# Cpcis_connectors_P4_P5_P6.net
KiCad netlist of a schematic drawn in Altium Designer
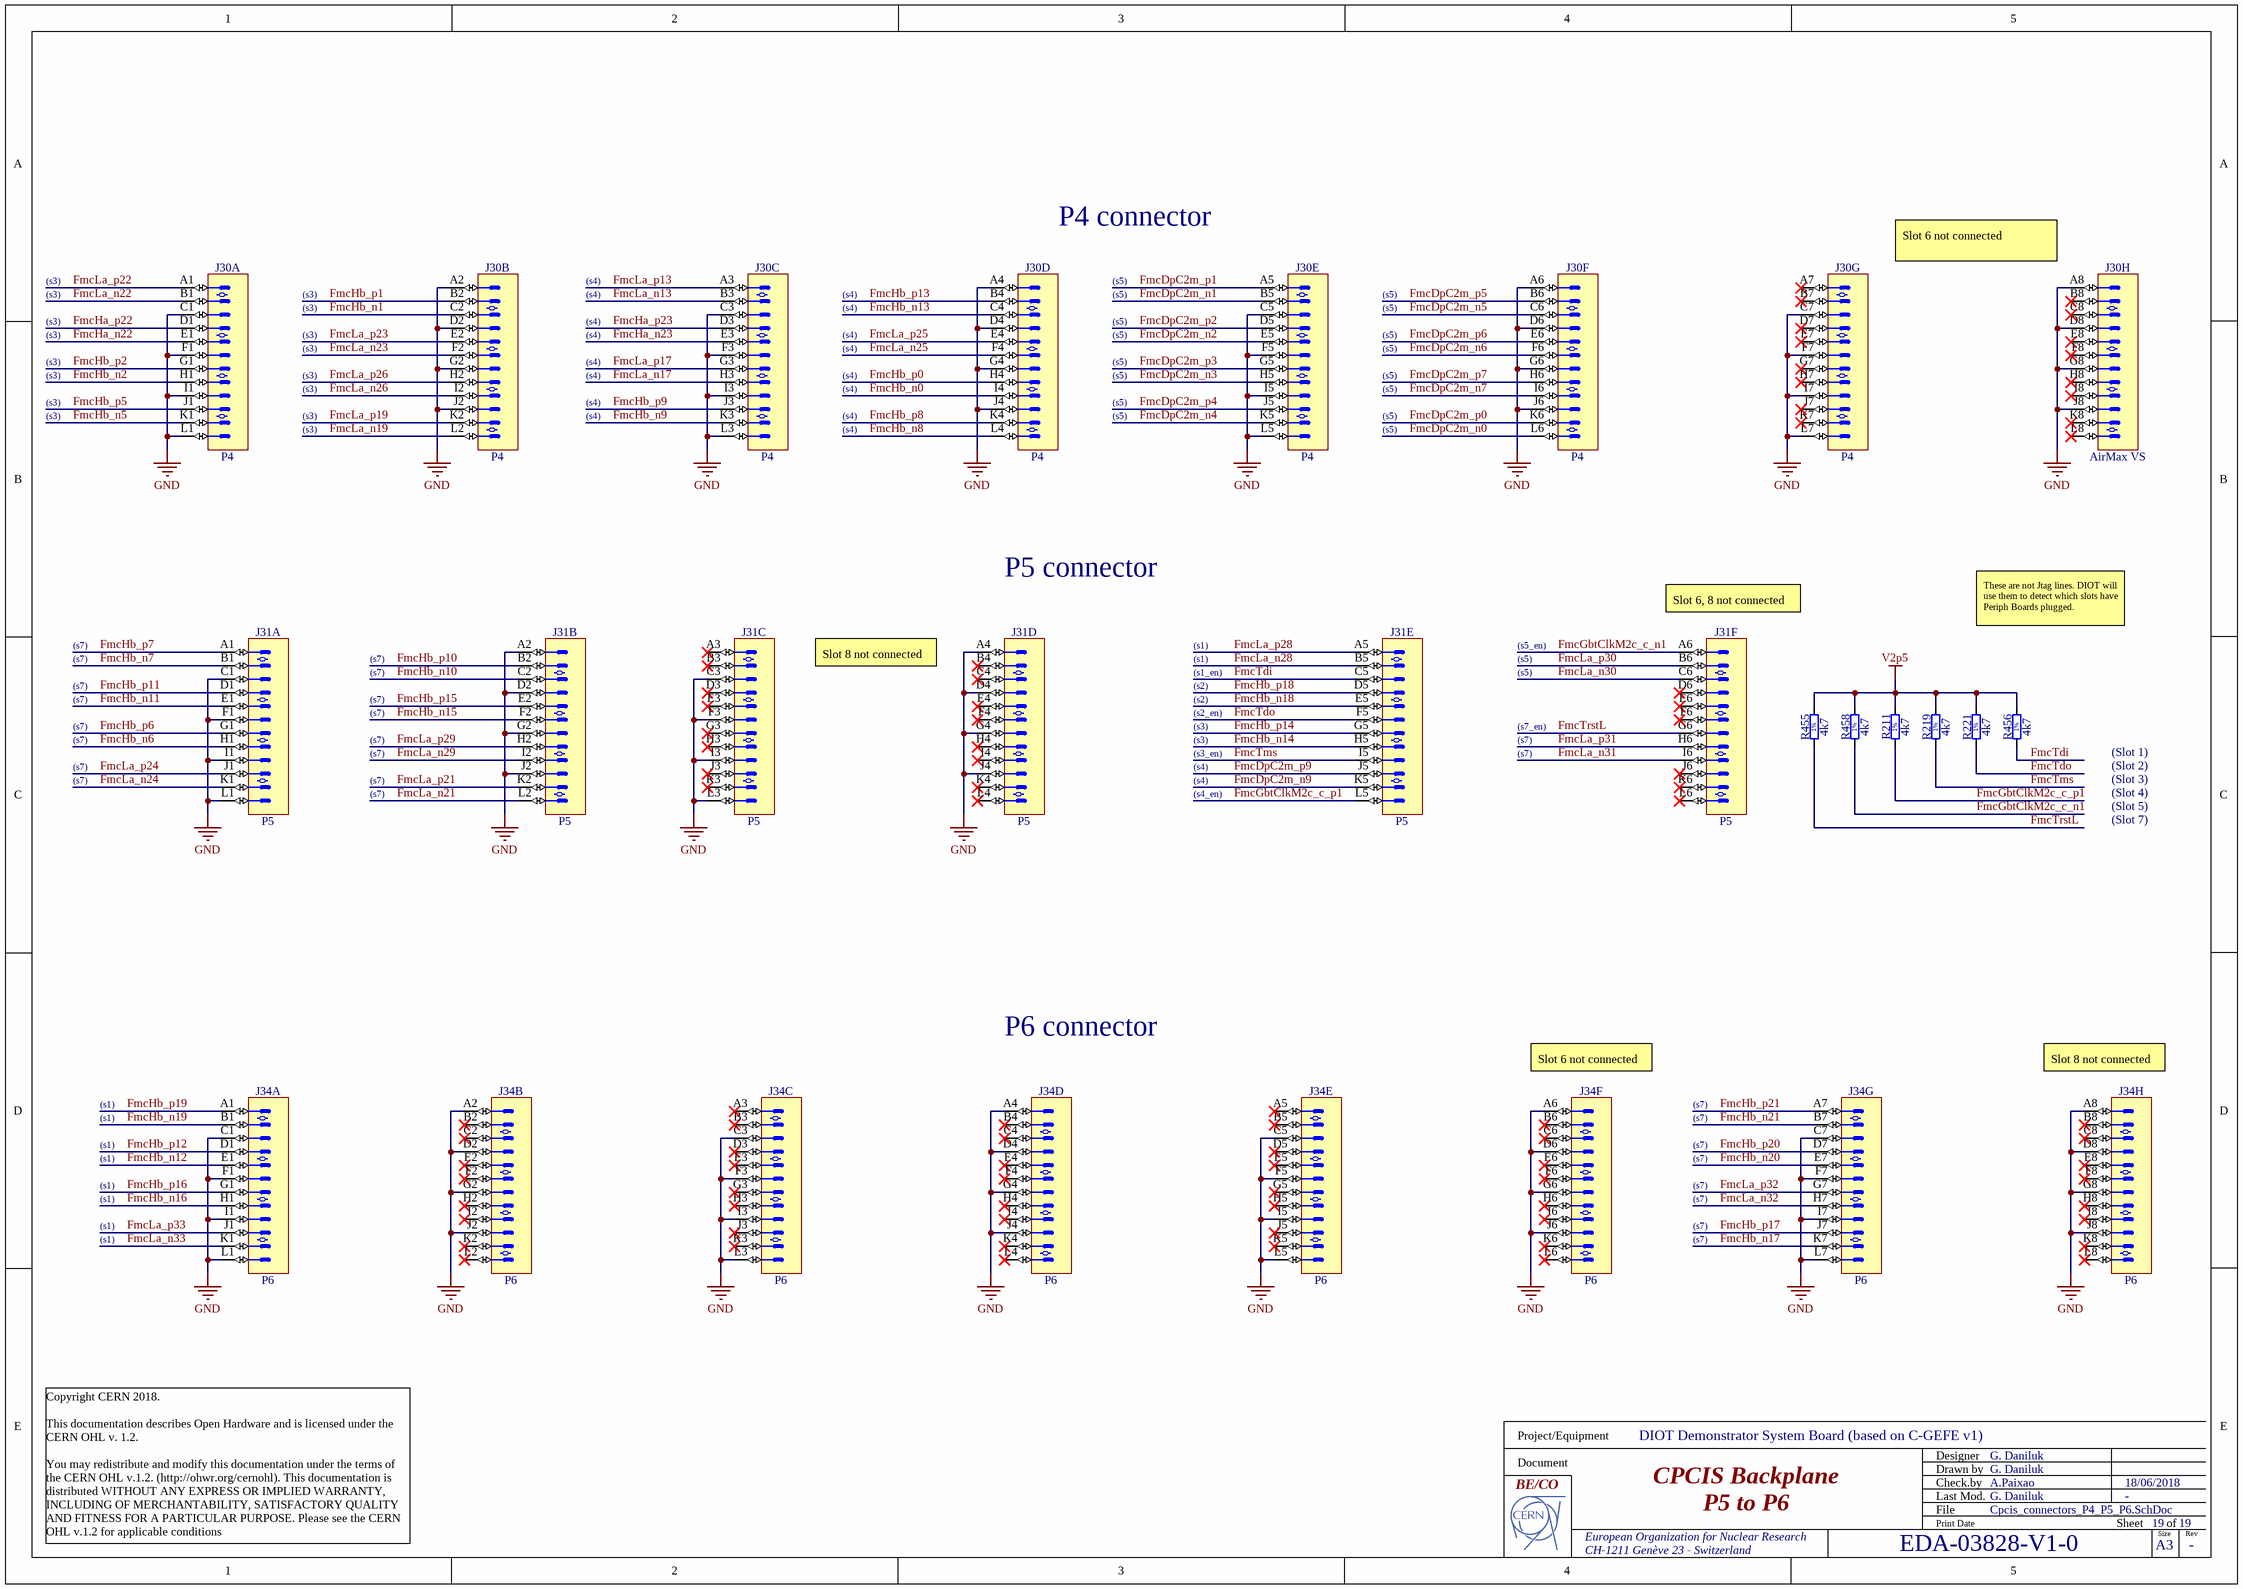
[diagram p0: Cpcis_connectors_P4_P5_P6.SchDoc]

(export (version "E")
  (design (tool "Eeschema 10.0.6"))
  (components
    (comp (ref "J30")
      (value "P4")
      (footprint "AMPHENOL_10052837-101LF")
      (description "96 Contacts Header, 8 Columns, 4 Pairs per Column")
      (fields
        (field (name "PART NUMBER") "AMPHENOL_10052837-101LF")
        (field (name "MANUFACTURER") "AMPHENOL")
        (field (name "AUTHOR") "CERN DEM MR")
      )
      (libsource (lib "Connectors") (part "AMPHENOL_10052837-101LF"))
    )
    (comp (ref "J31")
      (value "P5")
      (footprint "AMPHENOL_10052824-101LF")
      (description "72 Contacts Header, 6 Columns, 4 Pairs per Column")
      (fields
        (field (name "PART NUMBER") "AMPHENOL_10052824-101LF")
        (field (name "MANUFACTURER") "AMPHENOL")
        (field (name "AUTHOR") "CERN DEM JMW")
      )
      (libsource (lib "Connectors") (part "AMPHENOL_10052824-101LF"))
    )
    (comp (ref "J34")
      (value "P6")
      (footprint "AMPHENOL_10052838-101LF")
      (description "96 Contacts Header, 8 Columns, 4 Pairs per Column")
      (fields
        (field (name "PART NUMBER") "AMPHENOL_10052838-101LF")
        (field (name "MANUFACTURER") "AMPHENOL")
        (field (name "AUTHOR") "CERN DEM MR")
      )
      (libsource (lib "Connectors") (part "AMPHENOL_10052838-101LF"))
    )
    (comp (ref "R211")
      (value "4k7")
      (footprint "RESC1005X40N")
      (description "Resistor - 1%")
      (fields
        (field (name "PART NUMBER") "R0402_4K7_1%_0.0625W_100PPM")
        (field (name "POWER") "0.0625W")
        (field (name "AUTHOR") "CERN DEM JLC")
      )
      (libsource (lib "Resistors") (part "Resistor - 1%"))
    )
    (comp (ref "R219")
      (value "4k7")
      (footprint "RESC1005X40N")
      (description "Resistor - 1%")
      (fields
        (field (name "PART NUMBER") "R0402_4K7_1%_0.0625W_100PPM")
        (field (name "POWER") "0.0625W")
        (field (name "AUTHOR") "CERN DEM JLC")
      )
      (libsource (lib "Resistors") (part "Resistor - 1%"))
    )
    (comp (ref "R221")
      (value "4k7")
      (footprint "RESC1005X40N")
      (description "Resistor - 1%")
      (fields
        (field (name "PART NUMBER") "R0402_4K7_1%_0.0625W_100PPM")
        (field (name "POWER") "0.0625W")
        (field (name "AUTHOR") "CERN DEM JLC")
      )
      (libsource (lib "Resistors") (part "Resistor - 1%"))
    )
    (comp (ref "R455")
      (value "4k7")
      (footprint "RESC1005X40N")
      (description "Resistor - 1%")
      (fields
        (field (name "PART NUMBER") "R0402_4K7_1%_0.0625W_100PPM")
        (field (name "POWER") "0.0625W")
        (field (name "AUTHOR") "CERN DEM JLC")
      )
      (libsource (lib "Resistors") (part "Resistor - 1%"))
    )
    (comp (ref "R456")
      (value "4k7")
      (footprint "RESC1005X40N")
      (description "Resistor - 1%")
      (fields
        (field (name "PART NUMBER") "R0402_4K7_1%_0.0625W_100PPM")
        (field (name "POWER") "0.0625W")
        (field (name "AUTHOR") "CERN DEM JLC")
      )
      (libsource (lib "Resistors") (part "Resistor - 1%"))
    )
    (comp (ref "R458")
      (value "4k7")
      (footprint "RESC1005X40N")
      (description "Resistor - 1%")
      (fields
        (field (name "PART NUMBER") "R0402_4K7_1%_0.0625W_100PPM")
        (field (name "POWER") "0.0625W")
        (field (name "AUTHOR") "CERN DEM JLC")
      )
      (libsource (lib "Resistors") (part "Resistor - 1%"))
    )
  )
  (nets
    (net (code "1") (name "/FmcDpC2m_n0") (class "Default")
      (node (ref "J30") (pin "L6") (pinfunction "L6_L6") (pintype "bidirectional"))
    )
    (net (code "2") (name "/FmcDpC2m_n1") (class "Default")
      (node (ref "J30") (pin "B5") (pinfunction "B5_B5") (pintype "bidirectional"))
    )
    (net (code "3") (name "/FmcDpC2m_n2") (class "Default")
      (node (ref "J30") (pin "E5") (pinfunction "E5_E5") (pintype "bidirectional"))
    )
    (net (code "4") (name "/FmcDpC2m_n3") (class "Default")
      (node (ref "J30") (pin "H5") (pinfunction "H5_H5") (pintype "bidirectional"))
    )
    (net (code "5") (name "/FmcDpC2m_n4") (class "Default")
      (node (ref "J30") (pin "K5") (pinfunction "K5_K5") (pintype "bidirectional"))
    )
    (net (code "6") (name "/FmcDpC2m_n5") (class "Default")
      (node (ref "J30") (pin "C6") (pinfunction "C6_C6") (pintype "bidirectional"))
    )
    (net (code "7") (name "/FmcDpC2m_n6") (class "Default")
      (node (ref "J30") (pin "F6") (pinfunction "F6_F6") (pintype "bidirectional"))
    )
    (net (code "8") (name "/FmcDpC2m_n7") (class "Default")
      (node (ref "J30") (pin "I6") (pinfunction "I6_I6") (pintype "bidirectional"))
    )
    (net (code "9") (name "/FmcDpC2m_n9") (class "Default")
      (node (ref "J31") (pin "K5") (pinfunction "K5_K5") (pintype "bidirectional"))
    )
    (net (code "10") (name "/FmcDpC2m_p0") (class "Default")
      (node (ref "J30") (pin "K6") (pinfunction "K6_K6") (pintype "bidirectional"))
    )
    (net (code "11") (name "/FmcDpC2m_p1") (class "Default")
      (node (ref "J30") (pin "A5") (pinfunction "A5_A5") (pintype "bidirectional"))
    )
    (net (code "12") (name "/FmcDpC2m_p2") (class "Default")
      (node (ref "J30") (pin "D5") (pinfunction "D5_D5") (pintype "bidirectional"))
    )
    (net (code "13") (name "/FmcDpC2m_p3") (class "Default")
      (node (ref "J30") (pin "G5") (pinfunction "G5_G5") (pintype "bidirectional"))
    )
    (net (code "14") (name "/FmcDpC2m_p4") (class "Default")
      (node (ref "J30") (pin "J5") (pinfunction "J5_J5") (pintype "bidirectional"))
    )
    (net (code "15") (name "/FmcDpC2m_p5") (class "Default")
      (node (ref "J30") (pin "B6") (pinfunction "B6_B6") (pintype "bidirectional"))
    )
    (net (code "16") (name "/FmcDpC2m_p6") (class "Default")
      (node (ref "J30") (pin "E6") (pinfunction "E6_E6") (pintype "bidirectional"))
    )
    (net (code "17") (name "/FmcDpC2m_p7") (class "Default")
      (node (ref "J30") (pin "H6") (pinfunction "H6_H6") (pintype "bidirectional"))
    )
    (net (code "18") (name "/FmcDpC2m_p9") (class "Default")
      (node (ref "J31") (pin "J5") (pinfunction "J5_J5") (pintype "bidirectional"))
    )
    (net (code "19") (name "/FmcGbtClkM2c_c_n1") (class "Default")
      (node (ref "J31") (pin "A6") (pinfunction "A6_A6") (pintype "bidirectional"))
      (node (ref "R458") (pin "1") (pinfunction "1_1") (pintype "passive"))
    )
    (net (code "20") (name "/FmcGbtClkM2c_c_p1") (class "Default")
      (node (ref "J31") (pin "L5") (pinfunction "L5_L5") (pintype "bidirectional"))
      (node (ref "R211") (pin "1") (pinfunction "1_1") (pintype "passive"))
    )
    (net (code "21") (name "/FmcHa_n22") (class "Default")
      (node (ref "J30") (pin "E1") (pinfunction "E1_E1") (pintype "bidirectional"))
    )
    (net (code "22") (name "/FmcHa_n23") (class "Default")
      (node (ref "J30") (pin "E3") (pinfunction "E3_E3") (pintype "bidirectional"))
    )
    (net (code "23") (name "/FmcHa_p22") (class "Default")
      (node (ref "J30") (pin "D1") (pinfunction "D1_D1") (pintype "bidirectional"))
    )
    (net (code "24") (name "/FmcHa_p23") (class "Default")
      (node (ref "J30") (pin "D3") (pinfunction "D3_D3") (pintype "bidirectional"))
    )
    (net (code "25") (name "/FmcHb_n0") (class "Default")
      (node (ref "J30") (pin "I4") (pinfunction "I4_I4") (pintype "bidirectional"))
    )
    (net (code "26") (name "/FmcHb_n1") (class "Default")
      (node (ref "J30") (pin "C2") (pinfunction "C2_C2") (pintype "bidirectional"))
    )
    (net (code "27") (name "/FmcHb_n2") (class "Default")
      (node (ref "J30") (pin "H1") (pinfunction "H1_H1") (pintype "bidirectional"))
    )
    (net (code "28") (name "/FmcHb_n5") (class "Default")
      (node (ref "J30") (pin "K1") (pinfunction "K1_K1") (pintype "bidirectional"))
    )
    (net (code "29") (name "/FmcHb_n6") (class "Default")
      (node (ref "J31") (pin "H1") (pinfunction "H1_H1") (pintype "bidirectional"))
    )
    (net (code "30") (name "/FmcHb_n7") (class "Default")
      (node (ref "J31") (pin "B1") (pinfunction "B1_B1") (pintype "bidirectional"))
    )
    (net (code "31") (name "/FmcHb_n8") (class "Default")
      (node (ref "J30") (pin "L4") (pinfunction "L4_L4") (pintype "bidirectional"))
    )
    (net (code "32") (name "/FmcHb_n9") (class "Default")
      (node (ref "J30") (pin "K3") (pinfunction "K3_K3") (pintype "bidirectional"))
    )
    (net (code "33") (name "/FmcHb_n10") (class "Default")
      (node (ref "J31") (pin "C2") (pinfunction "C2_C2") (pintype "bidirectional"))
    )
    (net (code "34") (name "/FmcHb_n11") (class "Default")
      (node (ref "J31") (pin "E1") (pinfunction "E1_E1") (pintype "bidirectional"))
    )
    (net (code "35") (name "/FmcHb_n12") (class "Default")
      (node (ref "J34") (pin "E1") (pinfunction "E1_E1") (pintype "bidirectional"))
    )
    (net (code "36") (name "/FmcHb_n13") (class "Default")
      (node (ref "J30") (pin "C4") (pinfunction "C4_C4") (pintype "bidirectional"))
    )
    (net (code "37") (name "/FmcHb_n14") (class "Default")
      (node (ref "J31") (pin "H5") (pinfunction "H5_H5") (pintype "bidirectional"))
    )
    (net (code "38") (name "/FmcHb_n15") (class "Default")
      (node (ref "J31") (pin "F2") (pinfunction "F2_F2") (pintype "bidirectional"))
    )
    (net (code "39") (name "/FmcHb_n16") (class "Default")
      (node (ref "J34") (pin "H1") (pinfunction "H1_H1") (pintype "bidirectional"))
    )
    (net (code "40") (name "/FmcHb_n17") (class "Default")
      (node (ref "J34") (pin "K7") (pinfunction "K7_K7") (pintype "bidirectional"))
    )
    (net (code "41") (name "/FmcHb_n18") (class "Default")
      (node (ref "J31") (pin "E5") (pinfunction "E5_E5") (pintype "bidirectional"))
    )
    (net (code "42") (name "/FmcHb_n19") (class "Default")
      (node (ref "J34") (pin "B1") (pinfunction "B1_B1") (pintype "bidirectional"))
    )
    (net (code "43") (name "/FmcHb_n20") (class "Default")
      (node (ref "J34") (pin "E7") (pinfunction "E7_E7") (pintype "bidirectional"))
    )
    (net (code "44") (name "/FmcHb_n21") (class "Default")
      (node (ref "J34") (pin "B7") (pinfunction "B7_B7") (pintype "bidirectional"))
    )
    (net (code "45") (name "/FmcHb_p0") (class "Default")
      (node (ref "J30") (pin "H4") (pinfunction "H4_H4") (pintype "bidirectional"))
    )
    (net (code "46") (name "/FmcHb_p1") (class "Default")
      (node (ref "J30") (pin "B2") (pinfunction "B2_B2") (pintype "bidirectional"))
    )
    (net (code "47") (name "/FmcHb_p2") (class "Default")
      (node (ref "J30") (pin "G1") (pinfunction "G1_G1") (pintype "bidirectional"))
    )
    (net (code "48") (name "/FmcHb_p5") (class "Default")
      (node (ref "J30") (pin "J1") (pinfunction "J1_J1") (pintype "bidirectional"))
    )
    (net (code "49") (name "/FmcHb_p6") (class "Default")
      (node (ref "J31") (pin "G1") (pinfunction "G1_G1") (pintype "bidirectional"))
    )
    (net (code "50") (name "/FmcHb_p7") (class "Default")
      (node (ref "J31") (pin "A1") (pinfunction "A1_A1") (pintype "bidirectional"))
    )
    (net (code "51") (name "/FmcHb_p8") (class "Default")
      (node (ref "J30") (pin "K4") (pinfunction "K4_K4") (pintype "bidirectional"))
    )
    (net (code "52") (name "/FmcHb_p9") (class "Default")
      (node (ref "J30") (pin "J3") (pinfunction "J3_J3") (pintype "bidirectional"))
    )
    (net (code "53") (name "/FmcHb_p10") (class "Default")
      (node (ref "J31") (pin "B2") (pinfunction "B2_B2") (pintype "bidirectional"))
    )
    (net (code "54") (name "/FmcHb_p11") (class "Default")
      (node (ref "J31") (pin "D1") (pinfunction "D1_D1") (pintype "bidirectional"))
    )
    (net (code "55") (name "/FmcHb_p12") (class "Default")
      (node (ref "J34") (pin "D1") (pinfunction "D1_D1") (pintype "bidirectional"))
    )
    (net (code "56") (name "/FmcHb_p13") (class "Default")
      (node (ref "J30") (pin "B4") (pinfunction "B4_B4") (pintype "bidirectional"))
    )
    (net (code "57") (name "/FmcHb_p14") (class "Default")
      (node (ref "J31") (pin "G5") (pinfunction "G5_G5") (pintype "bidirectional"))
    )
    (net (code "58") (name "/FmcHb_p15") (class "Default")
      (node (ref "J31") (pin "E2") (pinfunction "E2_E2") (pintype "bidirectional"))
    )
    (net (code "59") (name "/FmcHb_p16") (class "Default")
      (node (ref "J34") (pin "G1") (pinfunction "G1_G1") (pintype "bidirectional"))
    )
    (net (code "60") (name "/FmcHb_p17") (class "Default")
      (node (ref "J34") (pin "J7") (pinfunction "J7_J7") (pintype "bidirectional"))
    )
    (net (code "61") (name "/FmcHb_p18") (class "Default")
      (node (ref "J31") (pin "D5") (pinfunction "D5_D5") (pintype "bidirectional"))
    )
    (net (code "62") (name "/FmcHb_p19") (class "Default")
      (node (ref "J34") (pin "A1") (pinfunction "A1_A1") (pintype "bidirectional"))
    )
    (net (code "63") (name "/FmcHb_p20") (class "Default")
      (node (ref "J34") (pin "D7") (pinfunction "D7_D7") (pintype "bidirectional"))
    )
    (net (code "64") (name "/FmcHb_p21") (class "Default")
      (node (ref "J34") (pin "A7") (pinfunction "A7_A7") (pintype "bidirectional"))
    )
    (net (code "65") (name "/FmcLa_n13") (class "Default")
      (node (ref "J30") (pin "B3") (pinfunction "B3_B3") (pintype "bidirectional"))
    )
    (net (code "66") (name "/FmcLa_n17") (class "Default")
      (node (ref "J30") (pin "H3") (pinfunction "H3_H3") (pintype "bidirectional"))
    )
    (net (code "67") (name "/FmcLa_n19") (class "Default")
      (node (ref "J30") (pin "L2") (pinfunction "L2_L2") (pintype "bidirectional"))
    )
    (net (code "68") (name "/FmcLa_n21") (class "Default")
      (node (ref "J31") (pin "L2") (pinfunction "L2_L2") (pintype "bidirectional"))
    )
    (net (code "69") (name "/FmcLa_n22") (class "Default")
      (node (ref "J30") (pin "B1") (pinfunction "B1_B1") (pintype "bidirectional"))
    )
    (net (code "70") (name "/FmcLa_n23") (class "Default")
      (node (ref "J30") (pin "F2") (pinfunction "F2_F2") (pintype "bidirectional"))
    )
    (net (code "71") (name "/FmcLa_n24") (class "Default")
      (node (ref "J31") (pin "K1") (pinfunction "K1_K1") (pintype "bidirectional"))
    )
    (net (code "72") (name "/FmcLa_n25") (class "Default")
      (node (ref "J30") (pin "F4") (pinfunction "F4_F4") (pintype "bidirectional"))
    )
    (net (code "73") (name "/FmcLa_n26") (class "Default")
      (node (ref "J30") (pin "I2") (pinfunction "I2_I2") (pintype "bidirectional"))
    )
    (net (code "74") (name "/FmcLa_n28") (class "Default")
      (node (ref "J31") (pin "B5") (pinfunction "B5_B5") (pintype "bidirectional"))
    )
    (net (code "75") (name "/FmcLa_n29") (class "Default")
      (node (ref "J31") (pin "I2") (pinfunction "I2_I2") (pintype "bidirectional"))
    )
    (net (code "76") (name "/FmcLa_n30") (class "Default")
      (node (ref "J31") (pin "C6") (pinfunction "C6_C6") (pintype "bidirectional"))
    )
    (net (code "77") (name "/FmcLa_n31") (class "Default")
      (node (ref "J31") (pin "I6") (pinfunction "I6_I6") (pintype "bidirectional"))
    )
    (net (code "78") (name "/FmcLa_n32") (class "Default")
      (node (ref "J34") (pin "H7") (pinfunction "H7_H7") (pintype "bidirectional"))
    )
    (net (code "79") (name "/FmcLa_n33") (class "Default")
      (node (ref "J34") (pin "K1") (pinfunction "K1_K1") (pintype "bidirectional"))
    )
    (net (code "80") (name "/FmcLa_p13") (class "Default")
      (node (ref "J30") (pin "A3") (pinfunction "A3_A3") (pintype "bidirectional"))
    )
    (net (code "81") (name "/FmcLa_p17") (class "Default")
      (node (ref "J30") (pin "G3") (pinfunction "G3_G3") (pintype "bidirectional"))
    )
    (net (code "82") (name "/FmcLa_p19") (class "Default")
      (node (ref "J30") (pin "K2") (pinfunction "K2_K2") (pintype "bidirectional"))
    )
    (net (code "83") (name "/FmcLa_p21") (class "Default")
      (node (ref "J31") (pin "K2") (pinfunction "K2_K2") (pintype "bidirectional"))
    )
    (net (code "84") (name "/FmcLa_p22") (class "Default")
      (node (ref "J30") (pin "A1") (pinfunction "A1_A1") (pintype "bidirectional"))
    )
    (net (code "85") (name "/FmcLa_p23") (class "Default")
      (node (ref "J30") (pin "E2") (pinfunction "E2_E2") (pintype "bidirectional"))
    )
    (net (code "86") (name "/FmcLa_p24") (class "Default")
      (node (ref "J31") (pin "J1") (pinfunction "J1_J1") (pintype "bidirectional"))
    )
    (net (code "87") (name "/FmcLa_p25") (class "Default")
      (node (ref "J30") (pin "E4") (pinfunction "E4_E4") (pintype "bidirectional"))
    )
    (net (code "88") (name "/FmcLa_p26") (class "Default")
      (node (ref "J30") (pin "H2") (pinfunction "H2_H2") (pintype "bidirectional"))
    )
    (net (code "89") (name "/FmcLa_p28") (class "Default")
      (node (ref "J31") (pin "A5") (pinfunction "A5_A5") (pintype "bidirectional"))
    )
    (net (code "90") (name "/FmcLa_p29") (class "Default")
      (node (ref "J31") (pin "H2") (pinfunction "H2_H2") (pintype "bidirectional"))
    )
    (net (code "91") (name "/FmcLa_p30") (class "Default")
      (node (ref "J31") (pin "B6") (pinfunction "B6_B6") (pintype "bidirectional"))
    )
    (net (code "92") (name "/FmcLa_p31") (class "Default")
      (node (ref "J31") (pin "H6") (pinfunction "H6_H6") (pintype "bidirectional"))
    )
    (net (code "93") (name "/FmcLa_p32") (class "Default")
      (node (ref "J34") (pin "G7") (pinfunction "G7_G7") (pintype "bidirectional"))
    )
    (net (code "94") (name "/FmcLa_p33") (class "Default")
      (node (ref "J34") (pin "J1") (pinfunction "J1_J1") (pintype "bidirectional"))
    )
    (net (code "95") (name "/FmcTdi") (class "Default")
      (node (ref "J31") (pin "C5") (pinfunction "C5_C5") (pintype "bidirectional"))
      (node (ref "R456") (pin "1") (pinfunction "1_1") (pintype "passive"))
    )
    (net (code "96") (name "/FmcTdo") (class "Default")
      (node (ref "J31") (pin "F5") (pinfunction "F5_F5") (pintype "bidirectional"))
      (node (ref "R221") (pin "1") (pinfunction "1_1") (pintype "passive"))
    )
    (net (code "97") (name "/FmcTms") (class "Default")
      (node (ref "J31") (pin "I5") (pinfunction "I5_I5") (pintype "bidirectional"))
      (node (ref "R219") (pin "1") (pinfunction "1_1") (pintype "passive"))
    )
    (net (code "98") (name "/FmcTrstL") (class "Default")
      (node (ref "J31") (pin "G6") (pinfunction "G6_G6") (pintype "bidirectional"))
      (node (ref "R455") (pin "1") (pinfunction "1_1") (pintype "passive"))
    )
    (net (code "99") (name "GND") (class "Default")
      (node (ref "J30") (pin "A2") (pinfunction "A2_A2") (pintype "bidirectional"))
      (node (ref "J30") (pin "A4") (pinfunction "A4_A4") (pintype "bidirectional"))
      (node (ref "J30") (pin "A6") (pinfunction "A6_A6") (pintype "bidirectional"))
      (node (ref "J30") (pin "A8") (pinfunction "A8_A8") (pintype "bidirectional"))
      (node (ref "J30") (pin "C1") (pinfunction "C1_C1") (pintype "bidirectional"))
      (node (ref "J30") (pin "C3") (pinfunction "C3_C3") (pintype "bidirectional"))
      (node (ref "J30") (pin "C5") (pinfunction "C5_C5") (pintype "bidirectional"))
      (node (ref "J30") (pin "C7") (pinfunction "C7_C7") (pintype "bidirectional"))
      (node (ref "J30") (pin "D2") (pinfunction "D2_D2") (pintype "bidirectional"))
      (node (ref "J30") (pin "D4") (pinfunction "D4_D4") (pintype "bidirectional"))
      (node (ref "J30") (pin "D6") (pinfunction "D6_D6") (pintype "bidirectional"))
      (node (ref "J30") (pin "D8") (pinfunction "D8_D8") (pintype "bidirectional"))
      (node (ref "J30") (pin "F1") (pinfunction "F1_F1") (pintype "bidirectional"))
      (node (ref "J30") (pin "F3") (pinfunction "F3_F3") (pintype "bidirectional"))
      (node (ref "J30") (pin "F5") (pinfunction "F5_F5") (pintype "bidirectional"))
      (node (ref "J30") (pin "F7") (pinfunction "F7_F7") (pintype "bidirectional"))
      (node (ref "J30") (pin "G2") (pinfunction "G2_G2") (pintype "bidirectional"))
      (node (ref "J30") (pin "G4") (pinfunction "G4_G4") (pintype "bidirectional"))
      (node (ref "J30") (pin "G6") (pinfunction "G6_G6") (pintype "bidirectional"))
      (node (ref "J30") (pin "G8") (pinfunction "G8_G8") (pintype "bidirectional"))
      (node (ref "J30") (pin "I1") (pinfunction "I1_I1") (pintype "bidirectional"))
      (node (ref "J30") (pin "I3") (pinfunction "I3_I3") (pintype "bidirectional"))
      (node (ref "J30") (pin "I5") (pinfunction "I5_I5") (pintype "bidirectional"))
      (node (ref "J30") (pin "I7") (pinfunction "I7_I7") (pintype "bidirectional"))
      (node (ref "J30") (pin "J2") (pinfunction "J2_J2") (pintype "bidirectional"))
      (node (ref "J30") (pin "J4") (pinfunction "J4_J4") (pintype "bidirectional"))
      (node (ref "J30") (pin "J6") (pinfunction "J6_J6") (pintype "bidirectional"))
      (node (ref "J30") (pin "J8") (pinfunction "J8_J8") (pintype "bidirectional"))
      (node (ref "J30") (pin "L1") (pinfunction "L1_L1") (pintype "bidirectional"))
      (node (ref "J30") (pin "L3") (pinfunction "L3_L3") (pintype "bidirectional"))
      (node (ref "J30") (pin "L5") (pinfunction "L5_L5") (pintype "bidirectional"))
      (node (ref "J30") (pin "L7") (pinfunction "L7_L7") (pintype "bidirectional"))
      (node (ref "J31") (pin "A2") (pinfunction "A2_A2") (pintype "bidirectional"))
      (node (ref "J31") (pin "A4") (pinfunction "A4_A4") (pintype "bidirectional"))
      (node (ref "J31") (pin "C1") (pinfunction "C1_C1") (pintype "bidirectional"))
      (node (ref "J31") (pin "C3") (pinfunction "C3_C3") (pintype "bidirectional"))
      (node (ref "J31") (pin "D2") (pinfunction "D2_D2") (pintype "bidirectional"))
      (node (ref "J31") (pin "D4") (pinfunction "D4_D4") (pintype "bidirectional"))
      (node (ref "J31") (pin "F1") (pinfunction "F1_F1") (pintype "bidirectional"))
      (node (ref "J31") (pin "F3") (pinfunction "F3_F3") (pintype "bidirectional"))
      (node (ref "J31") (pin "G2") (pinfunction "G2_G2") (pintype "bidirectional"))
      (node (ref "J31") (pin "G4") (pinfunction "G4_G4") (pintype "bidirectional"))
      (node (ref "J31") (pin "I1") (pinfunction "I1_I1") (pintype "bidirectional"))
      (node (ref "J31") (pin "I3") (pinfunction "I3_I3") (pintype "bidirectional"))
      (node (ref "J31") (pin "J2") (pinfunction "J2_J2") (pintype "bidirectional"))
      (node (ref "J31") (pin "J4") (pinfunction "J4_J4") (pintype "bidirectional"))
      (node (ref "J31") (pin "L1") (pinfunction "L1_L1") (pintype "bidirectional"))
      (node (ref "J31") (pin "L3") (pinfunction "L3_L3") (pintype "bidirectional"))
      (node (ref "J34") (pin "A2") (pinfunction "A2_A2") (pintype "bidirectional"))
      (node (ref "J34") (pin "A4") (pinfunction "A4_A4") (pintype "bidirectional"))
      (node (ref "J34") (pin "A6") (pinfunction "A6_A6") (pintype "bidirectional"))
      (node (ref "J34") (pin "A8") (pinfunction "A8_A8") (pintype "bidirectional"))
      (node (ref "J34") (pin "C1") (pinfunction "C1_C1") (pintype "bidirectional"))
      (node (ref "J34") (pin "C3") (pinfunction "C3_C3") (pintype "bidirectional"))
      (node (ref "J34") (pin "C5") (pinfunction "C5_C5") (pintype "bidirectional"))
      (node (ref "J34") (pin "C7") (pinfunction "C7_C7") (pintype "bidirectional"))
      (node (ref "J34") (pin "D2") (pinfunction "D2_D2") (pintype "bidirectional"))
      (node (ref "J34") (pin "D4") (pinfunction "D4_D4") (pintype "bidirectional"))
      (node (ref "J34") (pin "D6") (pinfunction "D6_D6") (pintype "bidirectional"))
      (node (ref "J34") (pin "D8") (pinfunction "D8_D8") (pintype "bidirectional"))
      (node (ref "J34") (pin "F1") (pinfunction "F1_F1") (pintype "bidirectional"))
      (node (ref "J34") (pin "F3") (pinfunction "F3_F3") (pintype "bidirectional"))
      (node (ref "J34") (pin "F5") (pinfunction "F5_F5") (pintype "bidirectional"))
      (node (ref "J34") (pin "F7") (pinfunction "F7_F7") (pintype "bidirectional"))
      (node (ref "J34") (pin "G2") (pinfunction "G2_G2") (pintype "bidirectional"))
      (node (ref "J34") (pin "G4") (pinfunction "G4_G4") (pintype "bidirectional"))
      (node (ref "J34") (pin "G6") (pinfunction "G6_G6") (pintype "bidirectional"))
      (node (ref "J34") (pin "G8") (pinfunction "G8_G8") (pintype "bidirectional"))
      (node (ref "J34") (pin "I1") (pinfunction "I1_I1") (pintype "bidirectional"))
      (node (ref "J34") (pin "I3") (pinfunction "I3_I3") (pintype "bidirectional"))
      (node (ref "J34") (pin "I5") (pinfunction "I5_I5") (pintype "bidirectional"))
      (node (ref "J34") (pin "I7") (pinfunction "I7_I7") (pintype "bidirectional"))
      (node (ref "J34") (pin "J2") (pinfunction "J2_J2") (pintype "bidirectional"))
      (node (ref "J34") (pin "J4") (pinfunction "J4_J4") (pintype "bidirectional"))
      (node (ref "J34") (pin "J6") (pinfunction "J6_J6") (pintype "bidirectional"))
      (node (ref "J34") (pin "J8") (pinfunction "J8_J8") (pintype "bidirectional"))
      (node (ref "J34") (pin "L1") (pinfunction "L1_L1") (pintype "bidirectional"))
      (node (ref "J34") (pin "L3") (pinfunction "L3_L3") (pintype "bidirectional"))
      (node (ref "J34") (pin "L5") (pinfunction "L5_L5") (pintype "bidirectional"))
      (node (ref "J34") (pin "L7") (pinfunction "L7_L7") (pintype "bidirectional"))
    )
    (net (code "100") (name "V2p5") (class "Default")
      (node (ref "R211") (pin "2") (pinfunction "2_2") (pintype "passive"))
      (node (ref "R219") (pin "2") (pinfunction "2_2") (pintype "passive"))
      (node (ref "R221") (pin "2") (pinfunction "2_2") (pintype "passive"))
      (node (ref "R455") (pin "2") (pinfunction "2_2") (pintype "passive"))
      (node (ref "R456") (pin "2") (pinfunction "2_2") (pintype "passive"))
      (node (ref "R458") (pin "2") (pinfunction "2_2") (pintype "passive"))
    )
    (net (code "101") (name "unconnected-(J30-PadA7)") (class "Default")
      (node (ref "J30") (pin "A7") (pinfunction "A7_A7") (pintype "bidirectional+no_connect"))
    )
    (net (code "102") (name "unconnected-(J30-PadB7)") (class "Default")
      (node (ref "J30") (pin "B7") (pinfunction "B7_B7") (pintype "bidirectional+no_connect"))
    )
    (net (code "103") (name "unconnected-(J30-PadB8)") (class "Default")
      (node (ref "J30") (pin "B8") (pinfunction "B8_B8") (pintype "bidirectional+no_connect"))
    )
    (net (code "104") (name "unconnected-(J30-PadC8)") (class "Default")
      (node (ref "J30") (pin "C8") (pinfunction "C8_C8") (pintype "bidirectional+no_connect"))
    )
    (net (code "105") (name "unconnected-(J30-PadD7)") (class "Default")
      (node (ref "J30") (pin "D7") (pinfunction "D7_D7") (pintype "bidirectional+no_connect"))
    )
    (net (code "106") (name "unconnected-(J30-PadE7)") (class "Default")
      (node (ref "J30") (pin "E7") (pinfunction "E7_E7") (pintype "bidirectional+no_connect"))
    )
    (net (code "107") (name "unconnected-(J30-PadE8)") (class "Default")
      (node (ref "J30") (pin "E8") (pinfunction "E8_E8") (pintype "bidirectional+no_connect"))
    )
    (net (code "108") (name "unconnected-(J30-PadF8)") (class "Default")
      (node (ref "J30") (pin "F8") (pinfunction "F8_F8") (pintype "bidirectional+no_connect"))
    )
    (net (code "109") (name "unconnected-(J30-PadG7)") (class "Default")
      (node (ref "J30") (pin "G7") (pinfunction "G7_G7") (pintype "bidirectional+no_connect"))
    )
    (net (code "110") (name "unconnected-(J30-PadH7)") (class "Default")
      (node (ref "J30") (pin "H7") (pinfunction "H7_H7") (pintype "bidirectional+no_connect"))
    )
    (net (code "111") (name "unconnected-(J30-PadH8)") (class "Default")
      (node (ref "J30") (pin "H8") (pinfunction "H8_H8") (pintype "bidirectional+no_connect"))
    )
    (net (code "112") (name "unconnected-(J30-PadI8)") (class "Default")
      (node (ref "J30") (pin "I8") (pinfunction "I8_I8") (pintype "bidirectional+no_connect"))
    )
    (net (code "113") (name "unconnected-(J30-PadJ7)") (class "Default")
      (node (ref "J30") (pin "J7") (pinfunction "J7_J7") (pintype "bidirectional+no_connect"))
    )
    (net (code "114") (name "unconnected-(J30-PadK7)") (class "Default")
      (node (ref "J30") (pin "K7") (pinfunction "K7_K7") (pintype "bidirectional+no_connect"))
    )
    (net (code "115") (name "unconnected-(J30-PadK8)") (class "Default")
      (node (ref "J30") (pin "K8") (pinfunction "K8_K8") (pintype "bidirectional+no_connect"))
    )
    (net (code "116") (name "unconnected-(J30-PadL8)") (class "Default")
      (node (ref "J30") (pin "L8") (pinfunction "L8_L8") (pintype "bidirectional+no_connect"))
    )
    (net (code "117") (name "unconnected-(J31-PadA3)") (class "Default")
      (node (ref "J31") (pin "A3") (pinfunction "A3_A3") (pintype "bidirectional+no_connect"))
    )
    (net (code "118") (name "unconnected-(J31-PadB3)") (class "Default")
      (node (ref "J31") (pin "B3") (pinfunction "B3_B3") (pintype "bidirectional+no_connect"))
    )
    (net (code "119") (name "unconnected-(J31-PadB4)") (class "Default")
      (node (ref "J31") (pin "B4") (pinfunction "B4_B4") (pintype "bidirectional+no_connect"))
    )
    (net (code "120") (name "unconnected-(J31-PadC4)") (class "Default")
      (node (ref "J31") (pin "C4") (pinfunction "C4_C4") (pintype "bidirectional+no_connect"))
    )
    (net (code "121") (name "unconnected-(J31-PadD3)") (class "Default")
      (node (ref "J31") (pin "D3") (pinfunction "D3_D3") (pintype "bidirectional+no_connect"))
    )
    (net (code "122") (name "unconnected-(J31-PadD6)") (class "Default")
      (node (ref "J31") (pin "D6") (pinfunction "D6_D6") (pintype "bidirectional+no_connect"))
    )
    (net (code "123") (name "unconnected-(J31-PadE3)") (class "Default")
      (node (ref "J31") (pin "E3") (pinfunction "E3_E3") (pintype "bidirectional+no_connect"))
    )
    (net (code "124") (name "unconnected-(J31-PadE4)") (class "Default")
      (node (ref "J31") (pin "E4") (pinfunction "E4_E4") (pintype "bidirectional+no_connect"))
    )
    (net (code "125") (name "unconnected-(J31-PadE6)") (class "Default")
      (node (ref "J31") (pin "E6") (pinfunction "E6_E6") (pintype "bidirectional+no_connect"))
    )
    (net (code "126") (name "unconnected-(J31-PadF4)") (class "Default")
      (node (ref "J31") (pin "F4") (pinfunction "F4_F4") (pintype "bidirectional+no_connect"))
    )
    (net (code "127") (name "unconnected-(J31-PadF6)") (class "Default")
      (node (ref "J31") (pin "F6") (pinfunction "F6_F6") (pintype "bidirectional+no_connect"))
    )
    (net (code "128") (name "unconnected-(J31-PadG3)") (class "Default")
      (node (ref "J31") (pin "G3") (pinfunction "G3_G3") (pintype "bidirectional+no_connect"))
    )
    (net (code "129") (name "unconnected-(J31-PadH3)") (class "Default")
      (node (ref "J31") (pin "H3") (pinfunction "H3_H3") (pintype "bidirectional+no_connect"))
    )
    (net (code "130") (name "unconnected-(J31-PadH4)") (class "Default")
      (node (ref "J31") (pin "H4") (pinfunction "H4_H4") (pintype "bidirectional+no_connect"))
    )
    (net (code "131") (name "unconnected-(J31-PadI4)") (class "Default")
      (node (ref "J31") (pin "I4") (pinfunction "I4_I4") (pintype "bidirectional+no_connect"))
    )
    (net (code "132") (name "unconnected-(J31-PadJ3)") (class "Default")
      (node (ref "J31") (pin "J3") (pinfunction "J3_J3") (pintype "bidirectional+no_connect"))
    )
    (net (code "133") (name "unconnected-(J31-PadJ6)") (class "Default")
      (node (ref "J31") (pin "J6") (pinfunction "J6_J6") (pintype "bidirectional+no_connect"))
    )
    (net (code "134") (name "unconnected-(J31-PadK3)") (class "Default")
      (node (ref "J31") (pin "K3") (pinfunction "K3_K3") (pintype "bidirectional+no_connect"))
    )
    (net (code "135") (name "unconnected-(J31-PadK4)") (class "Default")
      (node (ref "J31") (pin "K4") (pinfunction "K4_K4") (pintype "bidirectional+no_connect"))
    )
    (net (code "136") (name "unconnected-(J31-PadK6)") (class "Default")
      (node (ref "J31") (pin "K6") (pinfunction "K6_K6") (pintype "bidirectional+no_connect"))
    )
    (net (code "137") (name "unconnected-(J31-PadL4)") (class "Default")
      (node (ref "J31") (pin "L4") (pinfunction "L4_L4") (pintype "bidirectional+no_connect"))
    )
    (net (code "138") (name "unconnected-(J31-PadL6)") (class "Default")
      (node (ref "J31") (pin "L6") (pinfunction "L6_L6") (pintype "bidirectional+no_connect"))
    )
    (net (code "139") (name "unconnected-(J34-PadA3)") (class "Default")
      (node (ref "J34") (pin "A3") (pinfunction "A3_A3") (pintype "bidirectional+no_connect"))
    )
    (net (code "140") (name "unconnected-(J34-PadA5)") (class "Default")
      (node (ref "J34") (pin "A5") (pinfunction "A5_A5") (pintype "bidirectional+no_connect"))
    )
    (net (code "141") (name "unconnected-(J34-PadB2)") (class "Default")
      (node (ref "J34") (pin "B2") (pinfunction "B2_B2") (pintype "bidirectional+no_connect"))
    )
    (net (code "142") (name "unconnected-(J34-PadB3)") (class "Default")
      (node (ref "J34") (pin "B3") (pinfunction "B3_B3") (pintype "bidirectional+no_connect"))
    )
    (net (code "143") (name "unconnected-(J34-PadB4)") (class "Default")
      (node (ref "J34") (pin "B4") (pinfunction "B4_B4") (pintype "bidirectional+no_connect"))
    )
    (net (code "144") (name "unconnected-(J34-PadB5)") (class "Default")
      (node (ref "J34") (pin "B5") (pinfunction "B5_B5") (pintype "bidirectional+no_connect"))
    )
    (net (code "145") (name "unconnected-(J34-PadB6)") (class "Default")
      (node (ref "J34") (pin "B6") (pinfunction "B6_B6") (pintype "bidirectional+no_connect"))
    )
    (net (code "146") (name "unconnected-(J34-PadB8)") (class "Default")
      (node (ref "J34") (pin "B8") (pinfunction "B8_B8") (pintype "bidirectional+no_connect"))
    )
    (net (code "147") (name "unconnected-(J34-PadC2)") (class "Default")
      (node (ref "J34") (pin "C2") (pinfunction "C2_C2") (pintype "bidirectional+no_connect"))
    )
    (net (code "148") (name "unconnected-(J34-PadC4)") (class "Default")
      (node (ref "J34") (pin "C4") (pinfunction "C4_C4") (pintype "bidirectional+no_connect"))
    )
    (net (code "149") (name "unconnected-(J34-PadC6)") (class "Default")
      (node (ref "J34") (pin "C6") (pinfunction "C6_C6") (pintype "bidirectional+no_connect"))
    )
    (net (code "150") (name "unconnected-(J34-PadC8)") (class "Default")
      (node (ref "J34") (pin "C8") (pinfunction "C8_C8") (pintype "bidirectional+no_connect"))
    )
    (net (code "151") (name "unconnected-(J34-PadD3)") (class "Default")
      (node (ref "J34") (pin "D3") (pinfunction "D3_D3") (pintype "bidirectional+no_connect"))
    )
    (net (code "152") (name "unconnected-(J34-PadD5)") (class "Default")
      (node (ref "J34") (pin "D5") (pinfunction "D5_D5") (pintype "bidirectional+no_connect"))
    )
    (net (code "153") (name "unconnected-(J34-PadE2)") (class "Default")
      (node (ref "J34") (pin "E2") (pinfunction "E2_E2") (pintype "bidirectional+no_connect"))
    )
    (net (code "154") (name "unconnected-(J34-PadE3)") (class "Default")
      (node (ref "J34") (pin "E3") (pinfunction "E3_E3") (pintype "bidirectional+no_connect"))
    )
    (net (code "155") (name "unconnected-(J34-PadE4)") (class "Default")
      (node (ref "J34") (pin "E4") (pinfunction "E4_E4") (pintype "bidirectional+no_connect"))
    )
    (net (code "156") (name "unconnected-(J34-PadE5)") (class "Default")
      (node (ref "J34") (pin "E5") (pinfunction "E5_E5") (pintype "bidirectional+no_connect"))
    )
    (net (code "157") (name "unconnected-(J34-PadE6)") (class "Default")
      (node (ref "J34") (pin "E6") (pinfunction "E6_E6") (pintype "bidirectional+no_connect"))
    )
    (net (code "158") (name "unconnected-(J34-PadE8)") (class "Default")
      (node (ref "J34") (pin "E8") (pinfunction "E8_E8") (pintype "bidirectional+no_connect"))
    )
    (net (code "159") (name "unconnected-(J34-PadF2)") (class "Default")
      (node (ref "J34") (pin "F2") (pinfunction "F2_F2") (pintype "bidirectional+no_connect"))
    )
    (net (code "160") (name "unconnected-(J34-PadF4)") (class "Default")
      (node (ref "J34") (pin "F4") (pinfunction "F4_F4") (pintype "bidirectional+no_connect"))
    )
    (net (code "161") (name "unconnected-(J34-PadF6)") (class "Default")
      (node (ref "J34") (pin "F6") (pinfunction "F6_F6") (pintype "bidirectional+no_connect"))
    )
    (net (code "162") (name "unconnected-(J34-PadF8)") (class "Default")
      (node (ref "J34") (pin "F8") (pinfunction "F8_F8") (pintype "bidirectional+no_connect"))
    )
    (net (code "163") (name "unconnected-(J34-PadG3)") (class "Default")
      (node (ref "J34") (pin "G3") (pinfunction "G3_G3") (pintype "bidirectional+no_connect"))
    )
    (net (code "164") (name "unconnected-(J34-PadG5)") (class "Default")
      (node (ref "J34") (pin "G5") (pinfunction "G5_G5") (pintype "bidirectional+no_connect"))
    )
    (net (code "165") (name "unconnected-(J34-PadH2)") (class "Default")
      (node (ref "J34") (pin "H2") (pinfunction "H2_H2") (pintype "bidirectional+no_connect"))
    )
    (net (code "166") (name "unconnected-(J34-PadH3)") (class "Default")
      (node (ref "J34") (pin "H3") (pinfunction "H3_H3") (pintype "bidirectional+no_connect"))
    )
    (net (code "167") (name "unconnected-(J34-PadH4)") (class "Default")
      (node (ref "J34") (pin "H4") (pinfunction "H4_H4") (pintype "bidirectional+no_connect"))
    )
    (net (code "168") (name "unconnected-(J34-PadH5)") (class "Default")
      (node (ref "J34") (pin "H5") (pinfunction "H5_H5") (pintype "bidirectional+no_connect"))
    )
    (net (code "169") (name "unconnected-(J34-PadH6)") (class "Default")
      (node (ref "J34") (pin "H6") (pinfunction "H6_H6") (pintype "bidirectional+no_connect"))
    )
    (net (code "170") (name "unconnected-(J34-PadH8)") (class "Default")
      (node (ref "J34") (pin "H8") (pinfunction "H8_H8") (pintype "bidirectional+no_connect"))
    )
    (net (code "171") (name "unconnected-(J34-PadI2)") (class "Default")
      (node (ref "J34") (pin "I2") (pinfunction "I2_I2") (pintype "bidirectional+no_connect"))
    )
    (net (code "172") (name "unconnected-(J34-PadI4)") (class "Default")
      (node (ref "J34") (pin "I4") (pinfunction "I4_I4") (pintype "bidirectional+no_connect"))
    )
    (net (code "173") (name "unconnected-(J34-PadI6)") (class "Default")
      (node (ref "J34") (pin "I6") (pinfunction "I6_I6") (pintype "bidirectional+no_connect"))
    )
    (net (code "174") (name "unconnected-(J34-PadI8)") (class "Default")
      (node (ref "J34") (pin "I8") (pinfunction "I8_I8") (pintype "bidirectional+no_connect"))
    )
    (net (code "175") (name "unconnected-(J34-PadJ3)") (class "Default")
      (node (ref "J34") (pin "J3") (pinfunction "J3_J3") (pintype "bidirectional+no_connect"))
    )
    (net (code "176") (name "unconnected-(J34-PadJ5)") (class "Default")
      (node (ref "J34") (pin "J5") (pinfunction "J5_J5") (pintype "bidirectional+no_connect"))
    )
    (net (code "177") (name "unconnected-(J34-PadK2)") (class "Default")
      (node (ref "J34") (pin "K2") (pinfunction "K2_K2") (pintype "bidirectional+no_connect"))
    )
    (net (code "178") (name "unconnected-(J34-PadK3)") (class "Default")
      (node (ref "J34") (pin "K3") (pinfunction "K3_K3") (pintype "bidirectional+no_connect"))
    )
    (net (code "179") (name "unconnected-(J34-PadK4)") (class "Default")
      (node (ref "J34") (pin "K4") (pinfunction "K4_K4") (pintype "bidirectional+no_connect"))
    )
    (net (code "180") (name "unconnected-(J34-PadK5)") (class "Default")
      (node (ref "J34") (pin "K5") (pinfunction "K5_K5") (pintype "bidirectional+no_connect"))
    )
    (net (code "181") (name "unconnected-(J34-PadK6)") (class "Default")
      (node (ref "J34") (pin "K6") (pinfunction "K6_K6") (pintype "bidirectional+no_connect"))
    )
    (net (code "182") (name "unconnected-(J34-PadK8)") (class "Default")
      (node (ref "J34") (pin "K8") (pinfunction "K8_K8") (pintype "bidirectional+no_connect"))
    )
    (net (code "183") (name "unconnected-(J34-PadL2)") (class "Default")
      (node (ref "J34") (pin "L2") (pinfunction "L2_L2") (pintype "bidirectional+no_connect"))
    )
    (net (code "184") (name "unconnected-(J34-PadL4)") (class "Default")
      (node (ref "J34") (pin "L4") (pinfunction "L4_L4") (pintype "bidirectional+no_connect"))
    )
    (net (code "185") (name "unconnected-(J34-PadL6)") (class "Default")
      (node (ref "J34") (pin "L6") (pinfunction "L6_L6") (pintype "bidirectional+no_connect"))
    )
    (net (code "186") (name "unconnected-(J34-PadL8)") (class "Default")
      (node (ref "J34") (pin "L8") (pinfunction "L8_L8") (pintype "bidirectional+no_connect"))
    )
  )
)
